# DomoMod.net
KiCad netlist of a schematic drawn in EAGLE
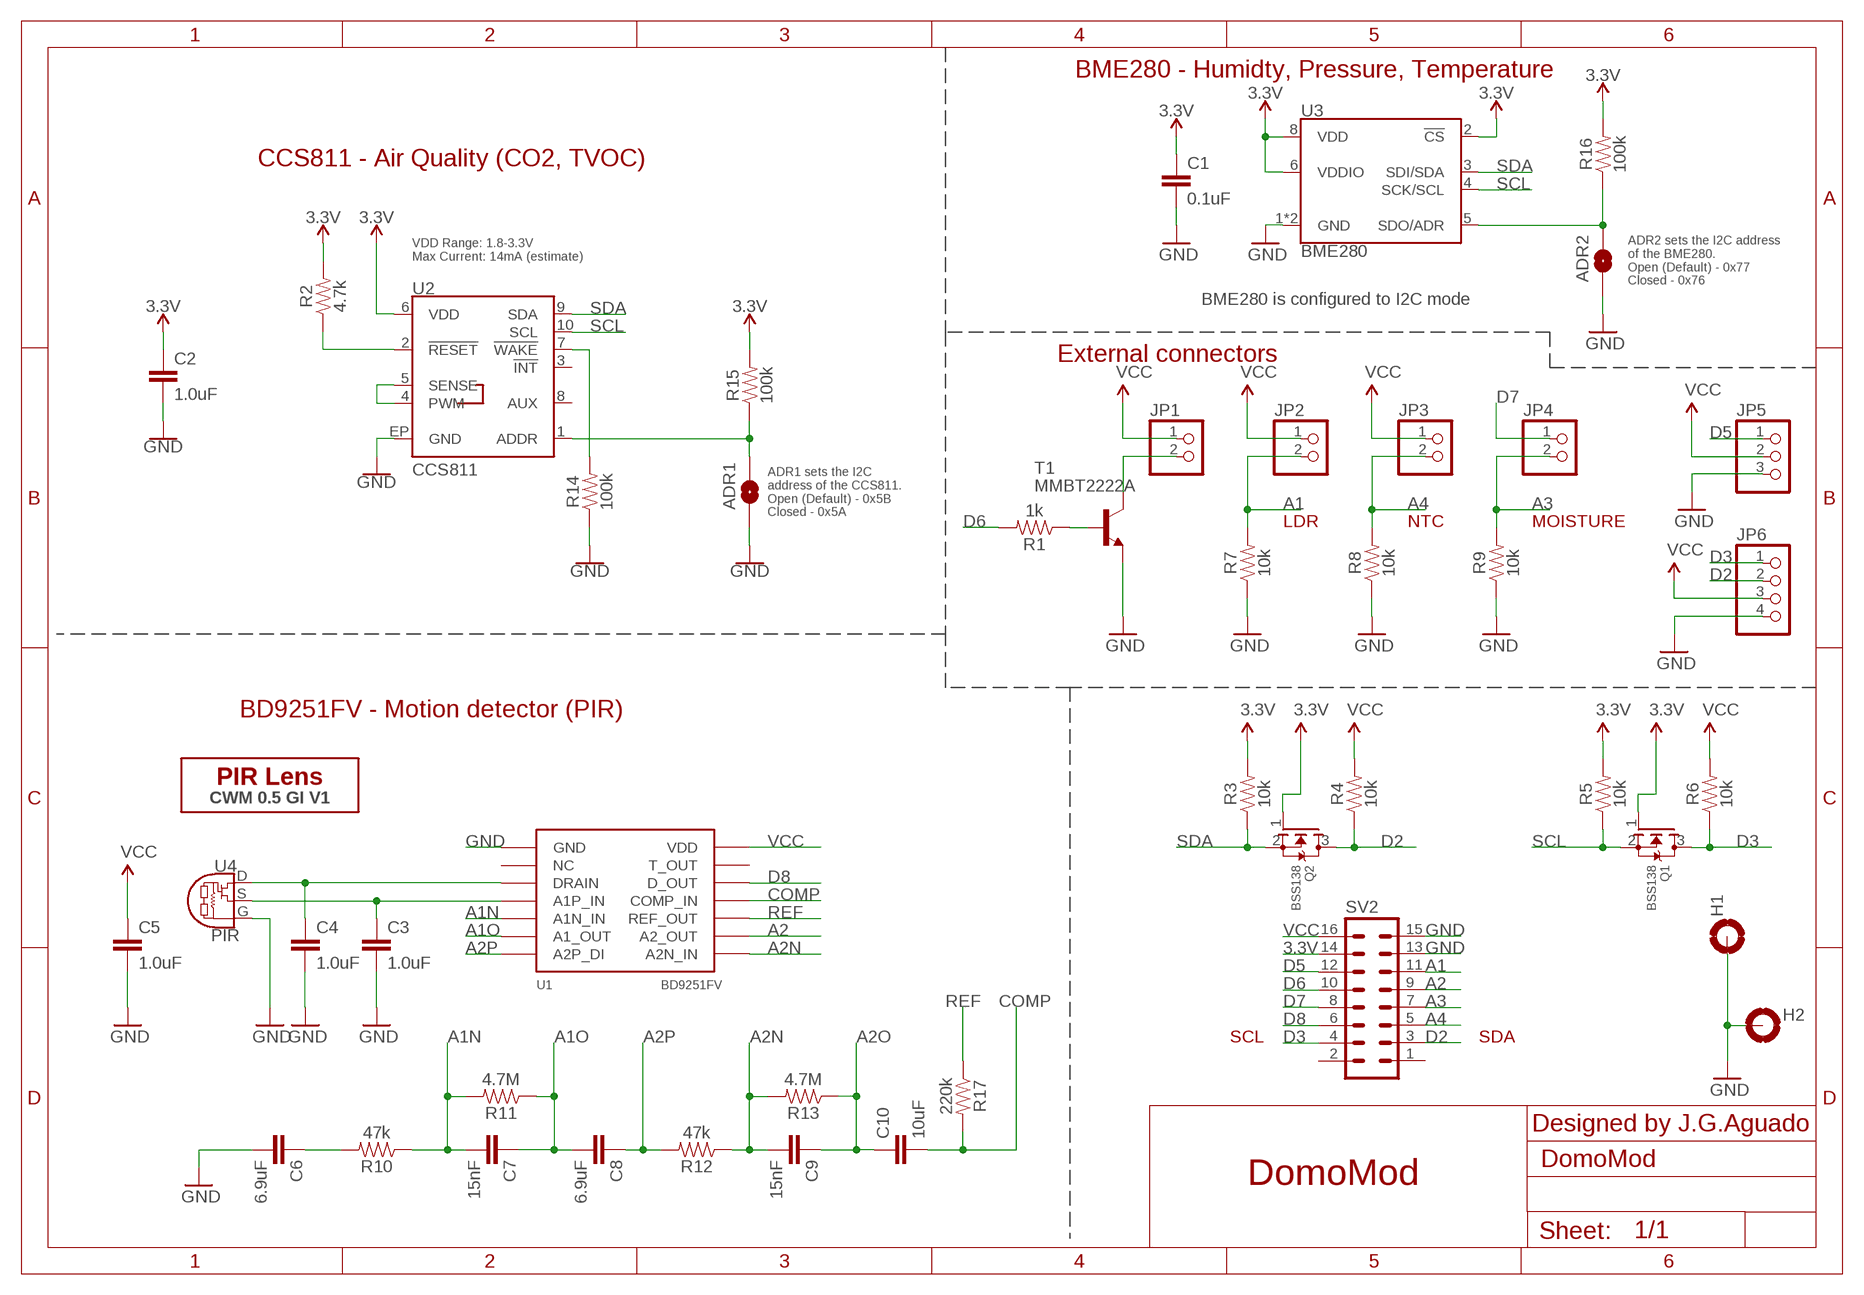
[diagram p0: schematic, sheet 1]

(export (version "E")
  (design (tool "Eeschema 10.0.6"))
  (components
    (comp (ref "ADR1")
      (value "JUMPER-SMT_2_NO_SILK")
      (footprint "eagle-import:SMT-JUMPER_2_NO_SILK")
      (libsource (lib "eagle-import") (part "JUMPER-SMT_2_NO_SILK"))
    )
    (comp (ref "ADR2")
      (value "JUMPER-SMT_2_NO_SILK")
      (footprint "eagle-import:SMT-JUMPER_2_NO_SILK")
      (libsource (lib "eagle-import") (part "JUMPER-SMT_2_NO_SILK"))
    )
    (comp (ref "C1")
      (value "0.1uF")
      (footprint "eagle-import:0603")
      (libsource (lib "eagle-import") (part "0.1UF-0603-25V-(+80/-20%)"))
    )
    (comp (ref "C2")
      (value "1.0uF")
      (footprint "eagle-import:0603")
      (libsource (lib "eagle-import") (part "1.0UF-0603-16V-10%"))
    )
    (comp (ref "C3")
      (value "1.0uF")
      (footprint "eagle-import:0603")
      (libsource (lib "eagle-import") (part "1.0UF-0603-16V-10%"))
    )
    (comp (ref "C4")
      (value "1.0uF")
      (footprint "eagle-import:0603")
      (libsource (lib "eagle-import") (part "1.0UF-0603-16V-10%"))
    )
    (comp (ref "C5")
      (value "1.0uF")
      (footprint "eagle-import:0603")
      (libsource (lib "eagle-import") (part "1.0UF-0603-16V-10%"))
    )
    (comp (ref "C6")
      (value "6.9uF")
      (footprint "eagle-import:0603")
      (libsource (lib "eagle-import") (part "1.0UF-0603-16V-10%"))
    )
    (comp (ref "C7")
      (value "15nF")
      (footprint "eagle-import:0603")
      (libsource (lib "eagle-import") (part "1.0UF-0603-16V-10%"))
    )
    (comp (ref "C8")
      (value "6.9uF")
      (footprint "eagle-import:0603")
      (libsource (lib "eagle-import") (part "1.0UF-0603-16V-10%"))
    )
    (comp (ref "C9")
      (value "15nF")
      (footprint "eagle-import:0603")
      (libsource (lib "eagle-import") (part "1.0UF-0603-16V-10%"))
    )
    (comp (ref "C10")
      (value "10uF")
      (footprint "eagle-import:0603")
      (libsource (lib "eagle-import") (part "1.0UF-0603-16V-10%"))
    )
    (comp (ref "H1")
      (value "MOUNT-PAD-ROUND3.2")
      (footprint "eagle-import:3,2-PAD")
      (libsource (lib "eagle-import") (part "MOUNT-PAD-ROUND3.2"))
    )
    (comp (ref "H2")
      (value "MOUNT-PAD-ROUND3.2")
      (footprint "eagle-import:3,2-PAD")
      (libsource (lib "eagle-import") (part "MOUNT-PAD-ROUND3.2"))
    )
    (comp (ref "JP1")
      (value "PINHD-1X2")
      (footprint "eagle-import:1X02")
      (libsource (lib "eagle-import") (part "PINHD-1X2"))
    )
    (comp (ref "JP2")
      (value "PINHD-1X2")
      (footprint "eagle-import:1X02")
      (libsource (lib "eagle-import") (part "PINHD-1X2"))
    )
    (comp (ref "JP3")
      (value "PINHD-1X2")
      (footprint "eagle-import:1X02")
      (libsource (lib "eagle-import") (part "PINHD-1X2"))
    )
    (comp (ref "JP4")
      (value "PINHD-1X2")
      (footprint "eagle-import:1X02")
      (libsource (lib "eagle-import") (part "PINHD-1X2"))
    )
    (comp (ref "JP5")
      (value "PINHD-1X3")
      (footprint "eagle-import:1X03")
      (libsource (lib "eagle-import") (part "PINHD-1X3"))
    )
    (comp (ref "JP6")
      (value "PINHD-1X4")
      (footprint "eagle-import:1X04")
      (libsource (lib "eagle-import") (part "PINHD-1X4"))
    )
    (comp (ref "Q1")
      (value "BSS138")
      (footprint "eagle-import:SOT23")
      (libsource (lib "eagle-import") (part "MOSFET-NREFLOW"))
    )
    (comp (ref "Q2")
      (value "BSS138")
      (footprint "eagle-import:SOT23")
      (libsource (lib "eagle-import") (part "MOSFET-NREFLOW"))
    )
    (comp (ref "R1")
      (value "1k")
      (footprint "eagle-import:0603")
      (libsource (lib "eagle-import") (part "100KOHM-0603-1/10W-1%"))
    )
    (comp (ref "R2")
      (value "4.7k")
      (footprint "eagle-import:0603")
      (libsource (lib "eagle-import") (part "4.7KOHM-0603-1/10W-1%"))
    )
    (comp (ref "R3")
      (value "10k")
      (footprint "eagle-import:0603")
      (libsource (lib "eagle-import") (part "100KOHM-0603-1/10W-1%"))
    )
    (comp (ref "R4")
      (value "10k")
      (footprint "eagle-import:0603")
      (libsource (lib "eagle-import") (part "100KOHM-0603-1/10W-1%"))
    )
    (comp (ref "R5")
      (value "10k")
      (footprint "eagle-import:0603")
      (libsource (lib "eagle-import") (part "100KOHM-0603-1/10W-1%"))
    )
    (comp (ref "R6")
      (value "10k")
      (footprint "eagle-import:0603")
      (libsource (lib "eagle-import") (part "100KOHM-0603-1/10W-1%"))
    )
    (comp (ref "R7")
      (value "10k")
      (footprint "eagle-import:0603")
      (libsource (lib "eagle-import") (part "100KOHM-0603-1/10W-1%"))
    )
    (comp (ref "R8")
      (value "10k")
      (footprint "eagle-import:0603")
      (libsource (lib "eagle-import") (part "100KOHM-0603-1/10W-1%"))
    )
    (comp (ref "R9")
      (value "10k")
      (footprint "eagle-import:0603")
      (libsource (lib "eagle-import") (part "100KOHM-0603-1/10W-1%"))
    )
    (comp (ref "R10")
      (value "47k")
      (footprint "eagle-import:0603")
      (libsource (lib "eagle-import") (part "100KOHM-0603-1/10W-1%"))
    )
    (comp (ref "R11")
      (value "4.7M")
      (footprint "eagle-import:0603")
      (libsource (lib "eagle-import") (part "100KOHM-0603-1/10W-1%"))
    )
    (comp (ref "R12")
      (value "47k")
      (footprint "eagle-import:0603")
      (libsource (lib "eagle-import") (part "100KOHM-0603-1/10W-1%"))
    )
    (comp (ref "R13")
      (value "4.7M")
      (footprint "eagle-import:0603")
      (libsource (lib "eagle-import") (part "100KOHM-0603-1/10W-1%"))
    )
    (comp (ref "R14")
      (value "100k")
      (footprint "eagle-import:0603")
      (libsource (lib "eagle-import") (part "100KOHM-0603-1/10W-1%"))
    )
    (comp (ref "R15")
      (value "100k")
      (footprint "eagle-import:0603")
      (libsource (lib "eagle-import") (part "100KOHM-0603-1/10W-1%"))
    )
    (comp (ref "R16")
      (value "100k")
      (footprint "eagle-import:0603")
      (libsource (lib "eagle-import") (part "100KOHM-0603-1/10W-1%"))
    )
    (comp (ref "R17")
      (value "220k")
      (footprint "eagle-import:0603")
      (libsource (lib "eagle-import") (part "100KOHM-0603-1/10W-1%"))
    )
    (comp (ref "SV2")
      (value "MA08-2")
      (footprint "eagle-import:MA08-2")
      (libsource (lib "eagle-import") (part "MA08-2"))
    )
    (comp (ref "T1")
      (value "MMBT2222A")
      (footprint "eagle-import:SOT23-BEC")
      (libsource (lib "eagle-import") (part "-NPN-SOT23-BECBC808"))
    )
    (comp (ref "U$1")
      (value "CWM 0.5 GI V1")
      (footprint "eagle-import:LENS-CWM-0.5-GI-V1")
      (libsource (lib "eagle-import") (part "PIR-LENSCWM-0.5-GI-V1"))
    )
    (comp (ref "U1")
      (value "BD9251FV")
      (footprint "eagle-import:TSSOP-14")
      (libsource (lib "eagle-import") (part "BD9251FV"))
    )
    (comp (ref "U2")
      (value "CCS811")
      (footprint "eagle-import:LGA10")
      (libsource (lib "eagle-import") (part "CCS811PRODUCTION"))
    )
    (comp (ref "U3")
      (value "BME280")
      (footprint "eagle-import:LGA-8-2.5X2.5")
      (libsource (lib "eagle-import") (part "BME280"))
    )
    (comp (ref "U4")
      (value "PIR")
      (footprint "eagle-import:PIR")
      (libsource (lib "eagle-import") (part "PIR"))
    )
  )
  (nets
    (net (code "1") (name "/A1") (class "Default")
      (node (ref "JP2") (pin "2") (pinfunction "2_2") (pintype "passive"))
      (node (ref "R7") (pin "2") (pinfunction "2_2") (pintype "passive"))
      (node (ref "SV2") (pin "11") (pinfunction "11_11") (pintype "passive"))
    )
    (net (code "2") (name "/A1N") (class "Default")
      (node (ref "C7") (pin "2") (pinfunction "2_2") (pintype "passive"))
      (node (ref "R10") (pin "1") (pinfunction "1_1") (pintype "passive"))
      (node (ref "R11") (pin "2") (pinfunction "2_2") (pintype "passive"))
      (node (ref "U1") (pin "5") (pinfunction "A1N_IN_5") (pintype "bidirectional"))
    )
    (net (code "3") (name "/A1O") (class "Default")
      (node (ref "C7") (pin "1") (pinfunction "1_1") (pintype "passive"))
      (node (ref "C8") (pin "2") (pinfunction "2_2") (pintype "passive"))
      (node (ref "R11") (pin "1") (pinfunction "1_1") (pintype "passive"))
      (node (ref "U1") (pin "6") (pinfunction "A1_OUT_6") (pintype "bidirectional"))
    )
    (net (code "4") (name "/A2") (class "Default")
      (node (ref "SV2") (pin "9") (pinfunction "9_9") (pintype "passive"))
      (node (ref "U1") (pin "9") (pinfunction "A2_OUT_9") (pintype "bidirectional"))
    )
    (net (code "5") (name "/A2N") (class "Default")
      (node (ref "C9") (pin "2") (pinfunction "2_2") (pintype "passive"))
      (node (ref "R12") (pin "1") (pinfunction "1_1") (pintype "passive"))
      (node (ref "R13") (pin "2") (pinfunction "2_2") (pintype "passive"))
      (node (ref "U1") (pin "8") (pinfunction "A2N_IN_8") (pintype "bidirectional"))
    )
    (net (code "6") (name "/A2O") (class "Default")
      (node (ref "C10") (pin "1") (pinfunction "1_1") (pintype "passive"))
      (node (ref "C9") (pin "1") (pinfunction "1_1") (pintype "passive"))
      (node (ref "R13") (pin "1") (pinfunction "1_1") (pintype "passive"))
    )
    (net (code "7") (name "/A2P") (class "Default")
      (node (ref "C8") (pin "1") (pinfunction "1_1") (pintype "passive"))
      (node (ref "R12") (pin "2") (pinfunction "2_2") (pintype "passive"))
      (node (ref "U1") (pin "7") (pinfunction "A2P_DI_7") (pintype "bidirectional"))
    )
    (net (code "8") (name "/A3") (class "Default")
      (node (ref "JP4") (pin "2") (pinfunction "2_2") (pintype "passive"))
      (node (ref "R9") (pin "2") (pinfunction "2_2") (pintype "passive"))
      (node (ref "SV2") (pin "7") (pinfunction "7_7") (pintype "passive"))
    )
    (net (code "9") (name "/A4") (class "Default")
      (node (ref "JP3") (pin "2") (pinfunction "2_2") (pintype "passive"))
      (node (ref "R8") (pin "2") (pinfunction "2_2") (pintype "passive"))
      (node (ref "SV2") (pin "5") (pinfunction "5_5") (pintype "passive"))
    )
    (net (code "10") (name "/COMP") (class "Default")
      (node (ref "C10") (pin "2") (pinfunction "2_2") (pintype "passive"))
      (node (ref "R17") (pin "2") (pinfunction "2_2") (pintype "passive"))
      (node (ref "U1") (pin "11") (pinfunction "COMP_IN_11") (pintype "bidirectional"))
    )
    (net (code "11") (name "/D2") (class "Default")
      (node (ref "JP6") (pin "2") (pinfunction "2_2") (pintype "passive"))
      (node (ref "Q2") (pin "3") (pinfunction "D_3") (pintype "bidirectional"))
      (node (ref "R4") (pin "1") (pinfunction "1_1") (pintype "passive"))
      (node (ref "SV2") (pin "3") (pinfunction "3_3") (pintype "passive"))
    )
    (net (code "12") (name "/D3") (class "Default")
      (node (ref "JP6") (pin "1") (pinfunction "1_1") (pintype "passive"))
      (node (ref "Q1") (pin "3") (pinfunction "D_3") (pintype "bidirectional"))
      (node (ref "R6") (pin "1") (pinfunction "1_1") (pintype "passive"))
      (node (ref "SV2") (pin "4") (pinfunction "4_4") (pintype "passive"))
    )
    (net (code "13") (name "/D5") (class "Default")
      (node (ref "JP5") (pin "1") (pinfunction "1_1") (pintype "passive"))
      (node (ref "SV2") (pin "12") (pinfunction "12_12") (pintype "passive"))
    )
    (net (code "14") (name "/D6") (class "Default")
      (node (ref "R1") (pin "2") (pinfunction "2_2") (pintype "passive"))
      (node (ref "SV2") (pin "10") (pinfunction "10_10") (pintype "passive"))
    )
    (net (code "15") (name "/D7") (class "Default")
      (node (ref "JP4") (pin "1") (pinfunction "1_1") (pintype "passive"))
      (node (ref "SV2") (pin "8") (pinfunction "8_8") (pintype "passive"))
    )
    (net (code "16") (name "/D8") (class "Default")
      (node (ref "SV2") (pin "6") (pinfunction "6_6") (pintype "passive"))
      (node (ref "U1") (pin "12") (pinfunction "D_OUT_12") (pintype "bidirectional"))
    )
    (net (code "17") (name "/REF") (class "Default")
      (node (ref "R17") (pin "1") (pinfunction "1_1") (pintype "passive"))
      (node (ref "U1") (pin "10") (pinfunction "REF_OUT_10") (pintype "bidirectional"))
    )
    (net (code "18") (name "/SCL") (class "Default")
      (node (ref "Q1") (pin "2") (pinfunction "S_2") (pintype "bidirectional"))
      (node (ref "R5") (pin "1") (pinfunction "1_1") (pintype "passive"))
      (node (ref "U2") (pin "10") (pinfunction "SCL_10") (pintype "bidirectional"))
      (node (ref "U3") (pin "4") (pinfunction "SCK/SCL_4") (pintype "bidirectional"))
    )
    (net (code "19") (name "/SDA") (class "Default")
      (node (ref "Q2") (pin "2") (pinfunction "S_2") (pintype "bidirectional"))
      (node (ref "R3") (pin "1") (pinfunction "1_1") (pintype "passive"))
      (node (ref "U2") (pin "9") (pinfunction "SDA_9") (pintype "bidirectional"))
      (node (ref "U3") (pin "3") (pinfunction "SDI/SDA_3") (pintype "bidirectional"))
    )
    (net (code "20") (name "3.3V") (class "Default")
      (node (ref "C1") (pin "1") (pinfunction "1_1") (pintype "passive"))
      (node (ref "C2") (pin "1") (pinfunction "1_1") (pintype "passive"))
      (node (ref "Q1") (pin "1") (pinfunction "G_1") (pintype "bidirectional"))
      (node (ref "Q2") (pin "1") (pinfunction "G_1") (pintype "bidirectional"))
      (node (ref "R15") (pin "2") (pinfunction "2_2") (pintype "passive"))
      (node (ref "R16") (pin "2") (pinfunction "2_2") (pintype "passive"))
      (node (ref "R2") (pin "2") (pinfunction "2_2") (pintype "passive"))
      (node (ref "R3") (pin "2") (pinfunction "2_2") (pintype "passive"))
      (node (ref "R5") (pin "2") (pinfunction "2_2") (pintype "passive"))
      (node (ref "SV2") (pin "14") (pinfunction "14_14") (pintype "passive"))
      (node (ref "U2") (pin "6") (pinfunction "VDD_6") (pintype "bidirectional"))
      (node (ref "U3") (pin "2") (pinfunction "~{CS}_2") (pintype "bidirectional"))
      (node (ref "U3") (pin "6") (pinfunction "VDDIO_6") (pintype "bidirectional"))
      (node (ref "U3") (pin "8") (pinfunction "VDD_8") (pintype "bidirectional"))
    )
    (net (code "21") (name "GND") (class "Default")
      (node (ref "ADR1") (pin "1") (pinfunction "1_1") (pintype "passive"))
      (node (ref "ADR2") (pin "1") (pinfunction "1_1") (pintype "passive"))
      (node (ref "C1") (pin "2") (pinfunction "2_2") (pintype "passive"))
      (node (ref "C2") (pin "2") (pinfunction "2_2") (pintype "passive"))
      (node (ref "C3") (pin "2") (pinfunction "2_2") (pintype "passive"))
      (node (ref "C4") (pin "2") (pinfunction "2_2") (pintype "passive"))
      (node (ref "C5") (pin "2") (pinfunction "2_2") (pintype "passive"))
      (node (ref "C6") (pin "2") (pinfunction "2_2") (pintype "passive"))
      (node (ref "H1") (pin "B3,2") (pinfunction "MOUNT_B3,2") (pintype "passive"))
      (node (ref "H2") (pin "B3,2") (pinfunction "MOUNT_B3,2") (pintype "passive"))
      (node (ref "JP5") (pin "3") (pinfunction "3_3") (pintype "passive"))
      (node (ref "JP6") (pin "4") (pinfunction "4_4") (pintype "passive"))
      (node (ref "R14") (pin "1") (pinfunction "1_1") (pintype "passive"))
      (node (ref "R7") (pin "1") (pinfunction "1_1") (pintype "passive"))
      (node (ref "R8") (pin "1") (pinfunction "1_1") (pintype "passive"))
      (node (ref "R9") (pin "1") (pinfunction "1_1") (pintype "passive"))
      (node (ref "SV2") (pin "13") (pinfunction "13_13") (pintype "passive"))
      (node (ref "SV2") (pin "15") (pinfunction "15_15") (pintype "passive"))
      (node (ref "T1") (pin "E") (pinfunction "E_E") (pintype "passive"))
      (node (ref "U1") (pin "1") (pinfunction "GND_1") (pintype "bidirectional"))
      (node (ref "U2") (pin "EP") (pinfunction "GND_EP") (pintype "bidirectional"))
      (node (ref "U3") (pin "1") (pinfunction "GND_1") (pintype "bidirectional"))
      (node (ref "U3") (pin "7") (pinfunction "GND_7") (pintype "bidirectional"))
      (node (ref "U4") (pin "G") (pinfunction "G_G") (pintype "bidirectional"))
    )
    (net (code "22") (name "Net-(C6-Pad1)") (class "Default")
      (node (ref "C6") (pin "1") (pinfunction "1_1") (pintype "passive"))
      (node (ref "R10") (pin "2") (pinfunction "2_2") (pintype "passive"))
    )
    (net (code "23") (name "Net-(JP1-Pad2)") (class "Default")
      (node (ref "JP1") (pin "2") (pinfunction "2_2") (pintype "passive"))
      (node (ref "T1") (pin "C") (pinfunction "C_C") (pintype "passive"))
    )
    (net (code "24") (name "Net-(R1-Pad1)") (class "Default")
      (node (ref "R1") (pin "1") (pinfunction "1_1") (pintype "passive"))
      (node (ref "T1") (pin "B") (pinfunction "B_B") (pintype "passive"))
    )
    (net (code "25") (name "Net-(U1-A1P_IN)") (class "Default")
      (node (ref "C3") (pin "1") (pinfunction "1_1") (pintype "passive"))
      (node (ref "U1") (pin "4") (pinfunction "A1P_IN_4") (pintype "bidirectional"))
      (node (ref "U4") (pin "S") (pinfunction "S_S") (pintype "bidirectional"))
    )
    (net (code "26") (name "Net-(U1-DRAIN)") (class "Default")
      (node (ref "C4") (pin "1") (pinfunction "1_1") (pintype "passive"))
      (node (ref "U1") (pin "3") (pinfunction "DRAIN_3") (pintype "bidirectional"))
      (node (ref "U4") (pin "D") (pinfunction "D_D") (pintype "bidirectional"))
    )
    (net (code "27") (name "Net-(U2-ADDR)") (class "Default")
      (node (ref "ADR1") (pin "2") (pinfunction "2_2") (pintype "passive"))
      (node (ref "R15") (pin "1") (pinfunction "1_1") (pintype "passive"))
      (node (ref "U2") (pin "1") (pinfunction "ADDR_1") (pintype "bidirectional"))
    )
    (net (code "28") (name "Net-(U2-PWM)") (class "Default")
      (node (ref "U2") (pin "4") (pinfunction "PWM_4") (pintype "bidirectional"))
      (node (ref "U2") (pin "5") (pinfunction "SENSE_5") (pintype "bidirectional"))
    )
    (net (code "29") (name "Net-(U2-~{RESET})") (class "Default")
      (node (ref "R2") (pin "1") (pinfunction "1_1") (pintype "passive"))
      (node (ref "U2") (pin "2") (pinfunction "~{RESET}_2") (pintype "bidirectional"))
    )
    (net (code "30") (name "Net-(U2-~{WAKE})") (class "Default")
      (node (ref "R14") (pin "2") (pinfunction "2_2") (pintype "passive"))
      (node (ref "U2") (pin "7") (pinfunction "~{WAKE}_7") (pintype "bidirectional"))
    )
    (net (code "31") (name "Net-(U3-SDO{slash}ADR)") (class "Default")
      (node (ref "ADR2") (pin "2") (pinfunction "2_2") (pintype "passive"))
      (node (ref "R16") (pin "1") (pinfunction "1_1") (pintype "passive"))
      (node (ref "U3") (pin "5") (pinfunction "SDO/ADR_5") (pintype "bidirectional"))
    )
    (net (code "32") (name "VCC") (class "Default")
      (node (ref "C5") (pin "1") (pinfunction "1_1") (pintype "passive"))
      (node (ref "JP1") (pin "1") (pinfunction "1_1") (pintype "passive"))
      (node (ref "JP2") (pin "1") (pinfunction "1_1") (pintype "passive"))
      (node (ref "JP3") (pin "1") (pinfunction "1_1") (pintype "passive"))
      (node (ref "JP5") (pin "2") (pinfunction "2_2") (pintype "passive"))
      (node (ref "JP6") (pin "3") (pinfunction "3_3") (pintype "passive"))
      (node (ref "R4") (pin "2") (pinfunction "2_2") (pintype "passive"))
      (node (ref "R6") (pin "2") (pinfunction "2_2") (pintype "passive"))
      (node (ref "SV2") (pin "16") (pinfunction "16_16") (pintype "passive"))
      (node (ref "U1") (pin "14") (pinfunction "VDD_14") (pintype "bidirectional"))
    )
    (net (code "33") (name "unconnected-(SV2-Pad1)") (class "Default")
      (node (ref "SV2") (pin "1") (pinfunction "1_1") (pintype "passive"))
    )
    (net (code "34") (name "unconnected-(SV2-Pad2)") (class "Default")
      (node (ref "SV2") (pin "2") (pinfunction "2_2") (pintype "passive"))
    )
    (net (code "35") (name "unconnected-(U1-NC-Pad2)") (class "Default")
      (node (ref "U1") (pin "2") (pinfunction "NC_2") (pintype "bidirectional"))
    )
    (net (code "36") (name "unconnected-(U1-T_OUT-Pad13)") (class "Default")
      (node (ref "U1") (pin "13") (pinfunction "T_OUT_13") (pintype "bidirectional"))
    )
    (net (code "37") (name "unconnected-(U2-AUX-Pad8)") (class "Default")
      (node (ref "U2") (pin "8") (pinfunction "AUX_8") (pintype "bidirectional"))
    )
    (net (code "38") (name "unconnected-(U2-~{INT}-Pad3)") (class "Default")
      (node (ref "U2") (pin "3") (pinfunction "~{INT}_3") (pintype "bidirectional"))
    )
  )
)
